# Misc.net
KiCad netlist of a schematic drawn in Altium Designer
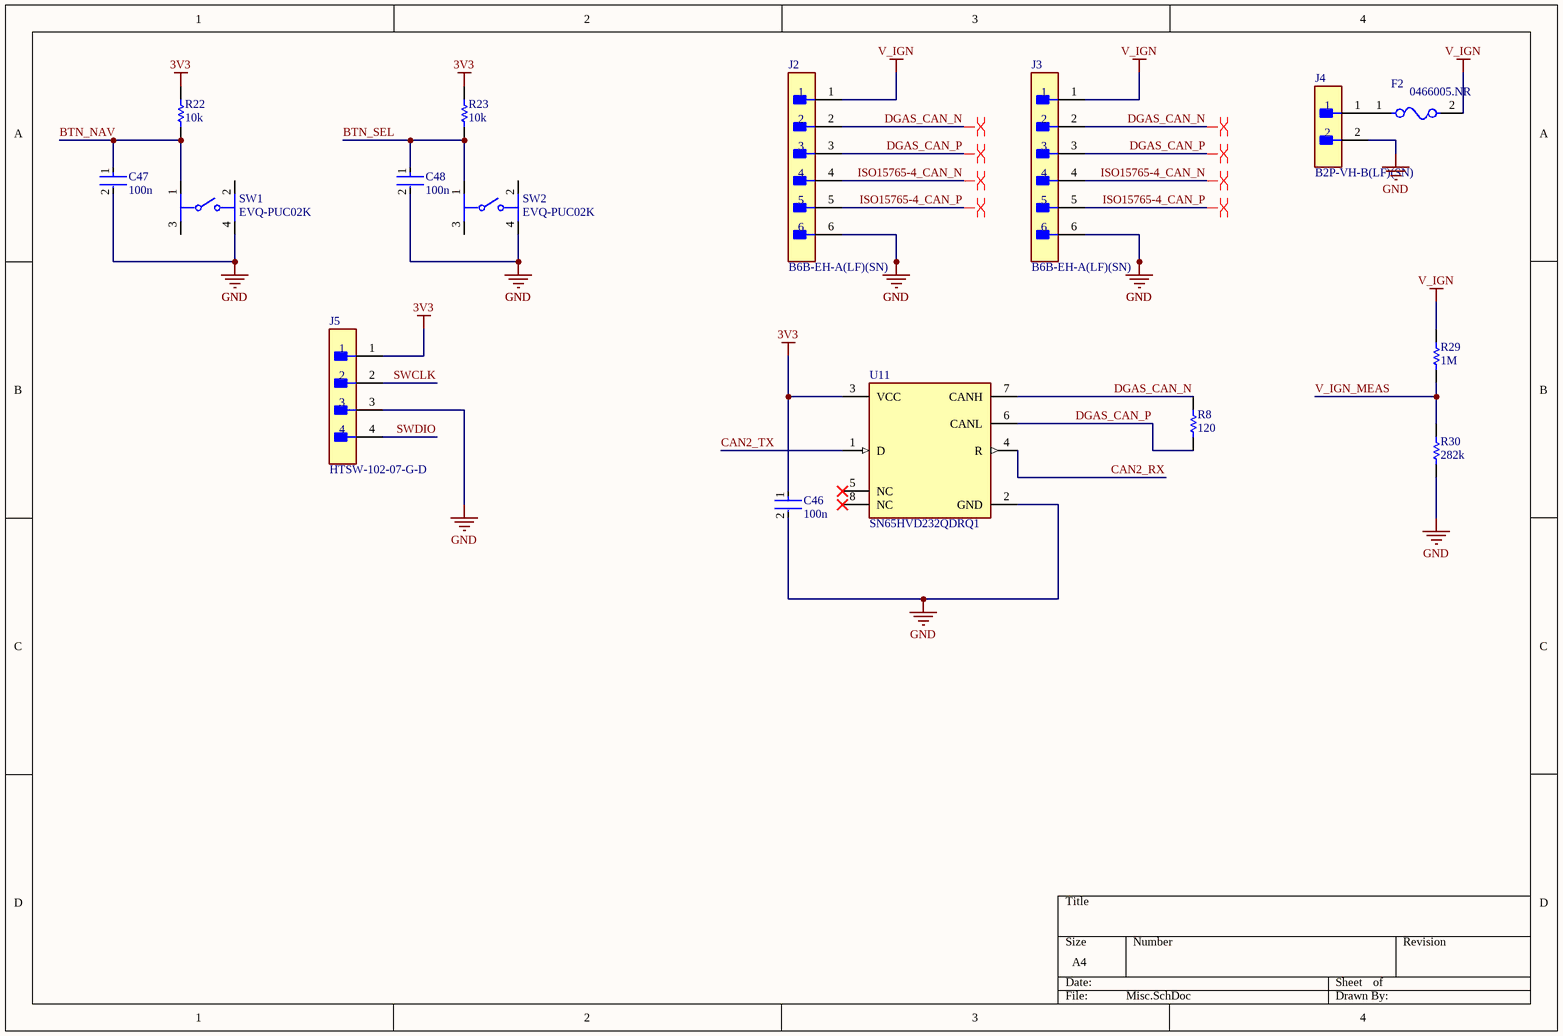
[diagram p0: Misc.SchDoc]

(export (version "E")
  (design (tool "Eeschema 10.0.6"))
  (components
    (comp (ref "C46")
      (value "100n")
      (footprint "FP-GRM188-0_1-e0_2_0_55-IPC_A")
      (description "Chip Multilayer Ceramic Capacitors for General Purpose, 0603, 10uF, X5R, 15%, 20%, 6.3V")
      (fields (field (name "VOLTAGE") "6.3V") (field (name "TOLERANCE") "20%"))
      (libsource (lib "Altium Content Vault") (part "02cd4be3c70576c341d710602a673aa"))
    )
    (comp (ref "C47")
      (value "100n")
      (footprint "FP-GRM188-0_1-e0_2_0_55-IPC_A")
      (description "Chip Multilayer Ceramic Capacitors for General Purpose, 0603, 10uF, X5R, 15%, 20%, 6.3V")
      (fields (field (name "VOLTAGE") "6.3V") (field (name "TOLERANCE") "20%"))
      (libsource (lib "Altium Content Vault") (part "02cd4be3c70576c341d710602a673aa"))
    )
    (comp (ref "C48")
      (value "100n")
      (footprint "FP-GRM188-0_1-e0_2_0_55-IPC_A")
      (description "Chip Multilayer Ceramic Capacitors for General Purpose, 0603, 10uF, X5R, 15%, 20%, 6.3V")
      (fields (field (name "VOLTAGE") "6.3V") (field (name "TOLERANCE") "20%"))
      (libsource (lib "Altium Content Vault") (part "02cd4be3c70576c341d710602a673aa"))
    )
    (comp (ref "F2")
      (value "0466005.NR")
      (footprint "FP-0466-MFG")
      (description "FUSE BOARD MNT 5A 32VAC/VDC 1206")
      (fields
        (field (name "OCTOPART") "https://octopart.com/0466005.nr-littelfuse-143206")
        (field (name "MANUFACTURER") "Littelfuse Inc")
      )
      (libsource (lib "Altium Content Vault") (part "5bcf9b9f640e542cf0359d10258e979"))
    )
    (comp (ref "J2")
      (value "B6B-EH-A(LF)(SN)")
      (footprint "FP-B6B-EH-A_LF_SN-MFG")
      (description "CONN HEADER VERT 6POS 2.5MM")
      (libsource (lib "Altium Content Vault") (part "f2cb566baf1c37ab5a3b8e90bbeafd6"))
    )
    (comp (ref "J3")
      (value "B6B-EH-A(LF)(SN)")
      (footprint "FP-B6B-EH-A_LF_SN-MFG")
      (description "CONN HEADER VERT 6POS 2.5MM")
      (libsource (lib "Altium Content Vault") (part "f2cb566baf1c37ab5a3b8e90bbeafd6"))
    )
    (comp (ref "J4")
      (value "B2P-VH-B(LF)(SN)")
      (footprint "FP-B2P-VH-B_LF_SN-MFG")
      (description "CONN HEADER VERT 2POS 3.96MM")
      (libsource (lib "Altium Content Vault") (part "3bc925449376181038e59eaffc5286c"))
    )
    (comp (ref "J5")
      (value "HTSW-102-07-G-D")
      (footprint "FP-HTSW-102-07-G-D-MFG")
      (description "CONN HEADER VERT 4POS 2.54MM")
      (fields
        (field (name "MANUFACTURER") "Samtec")
        (field (name "OCTOPART") "https://octopart.com/htsw-102-07-g-d-samtec-10531767")
      )
      (libsource (lib "Altium Content Vault") (part "299a8cea1bdcbc3624fe62c390fa72c"))
    )
    (comp (ref "R8")
      (value "120")
      (footprint "RESC1608X55X30ML15T15")
      (fields (field (name "PART NUMBER") "ERJ-3EKF1003V") (field (name "MANUFACTURER") "Panasonic"))
      (libsource (lib "Altium Content Vault") (part "RES"))
    )
    (comp (ref "R22")
      (value "10k")
      (footprint "RESC1609X50X30NL8T20")
      (description "Chip Resistor, 10 KOhm, +/- 1%, 100 mW, -55 to 155 degC, 0603 (1608 Metric), RoHS, Tape and Reel")
      (fields (field (name "MANUFACTURER") "Vishay Semiconductor"))
      (libsource (lib "Altium Content Vault") (part "RES-2"))
    )
    (comp (ref "R23")
      (value "10k")
      (footprint "RESC1609X50X30NL8T20")
      (description "Chip Resistor, 10 KOhm, +/- 1%, 100 mW, -55 to 155 degC, 0603 (1608 Metric), RoHS, Tape and Reel")
      (fields (field (name "MANUFACTURER") "Vishay Semiconductor"))
      (libsource (lib "Altium Content Vault") (part "RES-2"))
    )
    (comp (ref "R29")
      (value "1M")
      (footprint "RESC1609X50X30NL8T20")
      (description "Chip Resistor, 10 KOhm, +/- 1%, 100 mW, -55 to 155 degC, 0603 (1608 Metric), RoHS, Tape and Reel")
      (fields (field (name "MANUFACTURER") "Vishay Semiconductor"))
      (libsource (lib "Altium Content Vault") (part "RES-2"))
    )
    (comp (ref "R30")
      (value "282k")
      (footprint "RESC1609X50X30NL8T20")
      (description "Chip Resistor, 10 KOhm, +/- 1%, 100 mW, -55 to 155 degC, 0603 (1608 Metric), RoHS, Tape and Reel")
      (fields (field (name "MANUFACTURER") "Vishay Semiconductor"))
      (libsource (lib "Altium Content Vault") (part "RES-2"))
    )
    (comp (ref "SW1")
      (value "EVQ-PUC02K")
      (footprint "FP-EVQ-PUC02K-MFG")
      (description "SWITCH TACTILE SPST-NO 0.05A 12V")
      (libsource (lib "Altium Content Vault") (part "cb67941ecbda1860b707deecc235d4d"))
    )
    (comp (ref "SW2")
      (value "EVQ-PUC02K")
      (footprint "FP-EVQ-PUC02K-MFG")
      (description "SWITCH TACTILE SPST-NO 0.05A 12V")
      (libsource (lib "Altium Content Vault") (part "cb67941ecbda1860b707deecc235d4d"))
    )
    (comp (ref "U11")
      (value "SN65HVD232QDRQ1")
      (footprint "FP-D0008A-MFG")
      (description "IC TRANSCEIVER HALF 1/1 8SOIC")
      (libsource (lib "Altium Content Vault") (part "3bf20a45497b8b0096c58641b0f280c"))
    )
  )
  (nets
    (net (code "1") (name "/BTN_NAV") (class "Default")
      (node (ref "C47") (pin "1") (pinfunction "1_1") (pintype "passive"))
      (node (ref "R22") (pin "1") (pinfunction "1_1") (pintype "passive"))
      (node (ref "SW1") (pin "1") (pinfunction "1_1") (pintype "passive"))
    )
    (net (code "2") (name "/BTN_SEL") (class "Default")
      (node (ref "C48") (pin "1") (pinfunction "1_1") (pintype "passive"))
      (node (ref "R23") (pin "1") (pinfunction "1_1") (pintype "passive"))
      (node (ref "SW2") (pin "1") (pinfunction "1_1") (pintype "passive"))
    )
    (net (code "3") (name "/CAN2_RX") (class "Default")
      (node (ref "U11") (pin "4") (pinfunction "R_4") (pintype "output"))
    )
    (net (code "4") (name "/CAN2_TX") (class "Default")
      (node (ref "U11") (pin "1") (pinfunction "D_1") (pintype "input"))
    )
    (net (code "5") (name "/DGAS_CAN_N") (class "Default")
      (node (ref "J2") (pin "2") (pinfunction "2_2") (pintype "passive"))
      (node (ref "J3") (pin "2") (pinfunction "2_2") (pintype "passive"))
      (node (ref "R8") (pin "2") (pinfunction "2_2") (pintype "passive"))
      (node (ref "U11") (pin "7") (pinfunction "CANH_7") (pintype "passive"))
    )
    (net (code "6") (name "/DGAS_CAN_P") (class "Default")
      (node (ref "J2") (pin "3") (pinfunction "3_3") (pintype "passive"))
      (node (ref "J3") (pin "3") (pinfunction "3_3") (pintype "passive"))
      (node (ref "R8") (pin "1") (pinfunction "1_1") (pintype "passive"))
      (node (ref "U11") (pin "6") (pinfunction "CANL_6") (pintype "passive"))
    )
    (net (code "7") (name "/ISO15765-4_CAN_N") (class "Default")
      (node (ref "J2") (pin "4") (pinfunction "4_4") (pintype "passive"))
      (node (ref "J3") (pin "4") (pinfunction "4_4") (pintype "passive"))
    )
    (net (code "8") (name "/ISO15765-4_CAN_P") (class "Default")
      (node (ref "J2") (pin "5") (pinfunction "5_5") (pintype "passive"))
      (node (ref "J3") (pin "5") (pinfunction "5_5") (pintype "passive"))
    )
    (net (code "9") (name "/SWCLK") (class "Default")
      (node (ref "J5") (pin "2") (pinfunction "2_2") (pintype "passive"))
    )
    (net (code "10") (name "/SWDIO") (class "Default")
      (node (ref "J5") (pin "4") (pinfunction "4_4") (pintype "passive"))
    )
    (net (code "11") (name "/V_IGN_MEAS") (class "Default")
      (node (ref "R29") (pin "1") (pinfunction "1_1") (pintype "passive"))
      (node (ref "R30") (pin "2") (pinfunction "2_2") (pintype "passive"))
    )
    (net (code "12") (name "3V3") (class "Default")
      (node (ref "C46") (pin "1") (pinfunction "1_1") (pintype "passive"))
      (node (ref "J5") (pin "1") (pinfunction "1_1") (pintype "passive"))
      (node (ref "R22") (pin "2") (pinfunction "2_2") (pintype "passive"))
      (node (ref "R23") (pin "2") (pinfunction "2_2") (pintype "passive"))
      (node (ref "U11") (pin "3") (pinfunction "VCC_3") (pintype "power_in"))
    )
    (net (code "13") (name "GND") (class "Default")
      (node (ref "C46") (pin "2") (pinfunction "2_2") (pintype "passive"))
      (node (ref "C47") (pin "2") (pinfunction "2_2") (pintype "passive"))
      (node (ref "C48") (pin "2") (pinfunction "2_2") (pintype "passive"))
      (node (ref "J2") (pin "6") (pinfunction "6_6") (pintype "passive"))
      (node (ref "J3") (pin "6") (pinfunction "6_6") (pintype "passive"))
      (node (ref "J4") (pin "2") (pinfunction "2_2") (pintype "passive"))
      (node (ref "J5") (pin "3") (pinfunction "3_3") (pintype "passive"))
      (node (ref "R30") (pin "1") (pinfunction "1_1") (pintype "passive"))
      (node (ref "SW1") (pin "4") (pinfunction "4_4") (pintype "passive"))
      (node (ref "SW2") (pin "4") (pinfunction "4_4") (pintype "passive"))
      (node (ref "U11") (pin "2") (pinfunction "GND_2") (pintype "power_in"))
    )
    (net (code "14") (name "Net-(F2-Pad1)") (class "Default")
      (node (ref "F2") (pin "1") (pinfunction "1_1") (pintype "passive"))
      (node (ref "J4") (pin "1") (pinfunction "1_1") (pintype "passive"))
    )
    (net (code "15") (name "V_IGN") (class "Default")
      (node (ref "F2") (pin "2") (pinfunction "2_2") (pintype "passive"))
      (node (ref "J2") (pin "1") (pinfunction "1_1") (pintype "passive"))
      (node (ref "J3") (pin "1") (pinfunction "1_1") (pintype "passive"))
      (node (ref "R29") (pin "2") (pinfunction "2_2") (pintype "passive"))
    )
    (net (code "16") (name "unconnected-(SW1-Pad2)") (class "Default")
      (node (ref "SW1") (pin "2") (pinfunction "2_2") (pintype "passive"))
    )
    (net (code "17") (name "unconnected-(SW1-Pad3)") (class "Default")
      (node (ref "SW1") (pin "3") (pinfunction "3_3") (pintype "passive"))
    )
    (net (code "18") (name "unconnected-(SW2-Pad2)") (class "Default")
      (node (ref "SW2") (pin "2") (pinfunction "2_2") (pintype "passive"))
    )
    (net (code "19") (name "unconnected-(SW2-Pad3)") (class "Default")
      (node (ref "SW2") (pin "3") (pinfunction "3_3") (pintype "passive"))
    )
    (net (code "20") (name "unconnected-(U11-NC-Pad5)") (class "Default")
      (node (ref "U11") (pin "5") (pinfunction "NC_5") (pintype "passive+no_connect"))
    )
    (net (code "21") (name "unconnected-(U11-NC-Pad8)") (class "Default")
      (node (ref "U11") (pin "8") (pinfunction "NC_8") (pintype "passive+no_connect"))
    )
  )
)
